# 10w_LED_driver_auto.net
KiCad netlist of a schematic drawn in EAGLE
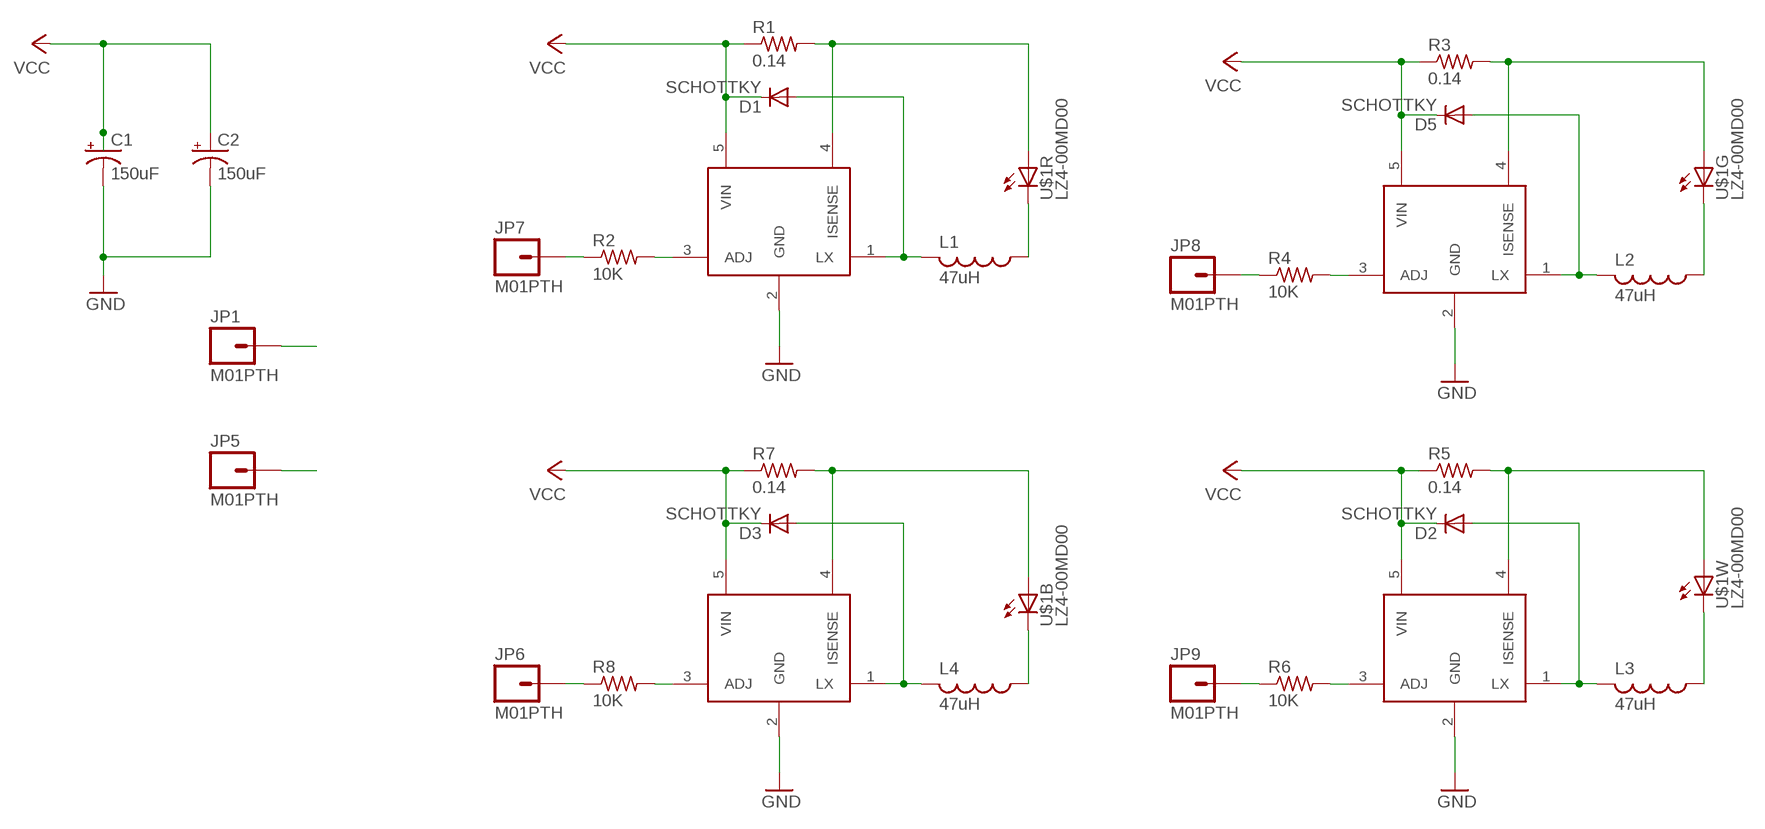
[diagram p0: schematic, sheet 1]

(export (version "E")
  (design (tool "Eeschema 10.0.6"))
  (components
    (comp (ref "C1")
      (value "150uF")
      (footprint "eagle-import:175TMP-0810")
      (libsource (lib "eagle-import") (part "CPOL-US175TMP-0810"))
    )
    (comp (ref "C2")
      (value "150uF")
      (footprint "eagle-import:175TMP-0810")
      (libsource (lib "eagle-import") (part "CPOL-US175TMP-0810"))
    )
    (comp (ref "D1")
      (value "SCHOTTKY")
      (footprint "eagle-import:DO214AC")
      (libsource (lib "eagle-import") (part "DIODE-DO214AC"))
    )
    (comp (ref "D2")
      (value "SCHOTTKY")
      (footprint "eagle-import:DO214AC")
      (libsource (lib "eagle-import") (part "DIODE-DO214AC"))
    )
    (comp (ref "D3")
      (value "SCHOTTKY")
      (footprint "eagle-import:DO214AC")
      (libsource (lib "eagle-import") (part "DIODE-DO214AC"))
    )
    (comp (ref "D5")
      (value "SCHOTTKY")
      (footprint "eagle-import:DO214AC")
      (libsource (lib "eagle-import") (part "DIODE-DO214AC"))
    )
    (comp (ref "JP1")
      (value "M01PTH")
      (footprint "eagle-import:1X01")
      (libsource (lib "eagle-import") (part "M01PTH"))
    )
    (comp (ref "JP5")
      (value "M01PTH")
      (footprint "eagle-import:1X01")
      (libsource (lib "eagle-import") (part "M01PTH"))
    )
    (comp (ref "JP6")
      (value "M01PTH")
      (footprint "eagle-import:1X01")
      (libsource (lib "eagle-import") (part "M01PTH"))
    )
    (comp (ref "JP7")
      (value "M01PTH")
      (footprint "eagle-import:1X01")
      (libsource (lib "eagle-import") (part "M01PTH"))
    )
    (comp (ref "JP8")
      (value "M01PTH")
      (footprint "eagle-import:1X01")
      (libsource (lib "eagle-import") (part "M01PTH"))
    )
    (comp (ref "JP9")
      (value "M01PTH")
      (footprint "eagle-import:1X01")
      (libsource (lib "eagle-import") (part "M01PTH"))
    )
    (comp (ref "L1")
      (value "47uH")
      (footprint "eagle-import:TDK6045")
      (libsource (lib "eagle-import") (part "L-US"))
    )
    (comp (ref "L2")
      (value "47uH")
      (footprint "eagle-import:TDK6045")
      (libsource (lib "eagle-import") (part "L-US"))
    )
    (comp (ref "L3")
      (value "47uH")
      (footprint "eagle-import:TDK6045")
      (libsource (lib "eagle-import") (part "L-US"))
    )
    (comp (ref "L4")
      (value "47uH")
      (footprint "eagle-import:TDK6045")
      (libsource (lib "eagle-import") (part "L-US"))
    )
    (comp (ref "R1")
      (value "0.14")
      (footprint "eagle-import:R0805")
      (libsource (lib "eagle-import") (part "R-US_R0805"))
    )
    (comp (ref "R2")
      (value "10K")
      (footprint "eagle-import:R0603")
      (libsource (lib "eagle-import") (part "R-US_R0603"))
    )
    (comp (ref "R3")
      (value "0.14")
      (footprint "eagle-import:R0805")
      (libsource (lib "eagle-import") (part "R-US_R0805"))
    )
    (comp (ref "R4")
      (value "10K")
      (footprint "eagle-import:R0603")
      (libsource (lib "eagle-import") (part "R-US_R0603"))
    )
    (comp (ref "R5")
      (value "0.14")
      (footprint "eagle-import:R0805")
      (libsource (lib "eagle-import") (part "R-US_R0805"))
    )
    (comp (ref "R6")
      (value "10K")
      (footprint "eagle-import:R0603")
      (libsource (lib "eagle-import") (part "R-US_R0603"))
    )
    (comp (ref "R7")
      (value "0.14")
      (footprint "eagle-import:R0805")
      (libsource (lib "eagle-import") (part "R-US_R0805"))
    )
    (comp (ref "R8")
      (value "10K")
      (footprint "eagle-import:R0603")
      (libsource (lib "eagle-import") (part "R-US_R0603"))
    )
    (comp (ref "U$1")
      (value "LZ4-00MD00")
      (footprint "eagle-import:LZ4-00MD0")
      (libsource (lib "eagle-import") (part "LZ4-00MD00"))
    )
    (comp (ref "U$2")
      (value "ZLED7000-LEDDRIVER")
      (footprint "eagle-import:SOT89-5")
      (libsource (lib "eagle-import") (part "ZLED7000-LEDDRIVER"))
    )
    (comp (ref "U$3")
      (value "ZLED7000-LEDDRIVER")
      (footprint "eagle-import:SOT89-5")
      (libsource (lib "eagle-import") (part "ZLED7000-LEDDRIVER"))
    )
    (comp (ref "U$4")
      (value "ZLED7000-LEDDRIVER")
      (footprint "eagle-import:SOT89-5")
      (libsource (lib "eagle-import") (part "ZLED7000-LEDDRIVER"))
    )
    (comp (ref "U$6")
      (value "ZLED7000-LEDDRIVER")
      (footprint "eagle-import:SOT89-5")
      (libsource (lib "eagle-import") (part "ZLED7000-LEDDRIVER"))
    )
  )
  (nets
    (net (code "1") (name "GND") (class "Default")
      (node (ref "C1") (pin "-") (pinfunction "-_-") (pintype "passive"))
      (node (ref "C2") (pin "-") (pinfunction "-_-") (pintype "passive"))
      (node (ref "JP5") (pin "1") (pinfunction "1_1") (pintype "passive"))
      (node (ref "U$2") (pin "2") (pinfunction "GND_2") (pintype "bidirectional"))
      (node (ref "U$3") (pin "2") (pinfunction "GND_2") (pintype "bidirectional"))
      (node (ref "U$4") (pin "2") (pinfunction "GND_2") (pintype "bidirectional"))
      (node (ref "U$6") (pin "2") (pinfunction "GND_2") (pintype "bidirectional"))
    )
    (net (code "2") (name "Net-(JP6-Pad1)") (class "Default")
      (node (ref "JP6") (pin "1") (pinfunction "1_1") (pintype "passive"))
      (node (ref "R8") (pin "1") (pinfunction "1_1") (pintype "passive"))
    )
    (net (code "3") (name "Net-(JP7-Pad1)") (class "Default")
      (node (ref "JP7") (pin "1") (pinfunction "1_1") (pintype "passive"))
      (node (ref "R2") (pin "1") (pinfunction "1_1") (pintype "passive"))
    )
    (net (code "4") (name "Net-(JP8-Pad1)") (class "Default")
      (node (ref "JP8") (pin "1") (pinfunction "1_1") (pintype "passive"))
      (node (ref "R4") (pin "1") (pinfunction "1_1") (pintype "passive"))
    )
    (net (code "5") (name "Net-(JP9-Pad1)") (class "Default")
      (node (ref "JP9") (pin "1") (pinfunction "1_1") (pintype "passive"))
      (node (ref "R6") (pin "1") (pinfunction "1_1") (pintype "passive"))
    )
    (net (code "6") (name "Net-(U$1A-A)") (class "Default")
      (node (ref "R7") (pin "2") (pinfunction "2_2") (pintype "passive"))
      (node (ref "U$1") (pin "7") (pinfunction "A_7") (pintype "passive"))
      (node (ref "U$4") (pin "4") (pinfunction "ISENSE_4") (pintype "bidirectional"))
    )
    (net (code "7") (name "Net-(U$1A-C)") (class "Default")
      (node (ref "L4") (pin "1") (pinfunction "1_1") (pintype "passive"))
      (node (ref "U$1") (pin "8") (pinfunction "C_8") (pintype "passive"))
    )
    (net (code "8") (name "Net-(U$1B-A)") (class "Default")
      (node (ref "R3") (pin "2") (pinfunction "2_2") (pintype "passive"))
      (node (ref "U$1") (pin "5") (pinfunction "A_5") (pintype "passive"))
      (node (ref "U$6") (pin "4") (pinfunction "ISENSE_4") (pintype "bidirectional"))
    )
    (net (code "9") (name "Net-(U$1B-C)") (class "Default")
      (node (ref "L2") (pin "1") (pinfunction "1_1") (pintype "passive"))
      (node (ref "U$1") (pin "6") (pinfunction "C_6") (pintype "passive"))
    )
    (net (code "10") (name "Net-(U$1C-A)") (class "Default")
      (node (ref "R1") (pin "2") (pinfunction "2_2") (pintype "passive"))
      (node (ref "U$1") (pin "3") (pinfunction "A_3") (pintype "passive"))
      (node (ref "U$2") (pin "4") (pinfunction "ISENSE_4") (pintype "bidirectional"))
    )
    (net (code "11") (name "Net-(U$1C-C)") (class "Default")
      (node (ref "L1") (pin "1") (pinfunction "1_1") (pintype "passive"))
      (node (ref "U$1") (pin "4") (pinfunction "C_4") (pintype "passive"))
    )
    (net (code "12") (name "Net-(U$1D-A)") (class "Default")
      (node (ref "R5") (pin "2") (pinfunction "2_2") (pintype "passive"))
      (node (ref "U$1") (pin "1") (pinfunction "A_1") (pintype "passive"))
      (node (ref "U$3") (pin "4") (pinfunction "ISENSE_4") (pintype "bidirectional"))
    )
    (net (code "13") (name "Net-(U$1D-C)") (class "Default")
      (node (ref "L3") (pin "1") (pinfunction "1_1") (pintype "passive"))
      (node (ref "U$1") (pin "2") (pinfunction "C_2") (pintype "passive"))
    )
    (net (code "14") (name "Net-(U$2-ADJ)") (class "Default")
      (node (ref "R2") (pin "2") (pinfunction "2_2") (pintype "passive"))
      (node (ref "U$2") (pin "3") (pinfunction "ADJ_3") (pintype "bidirectional"))
    )
    (net (code "15") (name "Net-(U$2-LX)") (class "Default")
      (node (ref "D1") (pin "A") (pinfunction "A_A") (pintype "passive"))
      (node (ref "L1") (pin "2") (pinfunction "2_2") (pintype "passive"))
      (node (ref "U$2") (pin "1") (pinfunction "LX_1") (pintype "bidirectional"))
    )
    (net (code "16") (name "Net-(U$3-ADJ)") (class "Default")
      (node (ref "R6") (pin "2") (pinfunction "2_2") (pintype "passive"))
      (node (ref "U$3") (pin "3") (pinfunction "ADJ_3") (pintype "bidirectional"))
    )
    (net (code "17") (name "Net-(U$3-LX)") (class "Default")
      (node (ref "D2") (pin "A") (pinfunction "A_A") (pintype "passive"))
      (node (ref "L3") (pin "2") (pinfunction "2_2") (pintype "passive"))
      (node (ref "U$3") (pin "1") (pinfunction "LX_1") (pintype "bidirectional"))
    )
    (net (code "18") (name "Net-(U$4-ADJ)") (class "Default")
      (node (ref "R8") (pin "2") (pinfunction "2_2") (pintype "passive"))
      (node (ref "U$4") (pin "3") (pinfunction "ADJ_3") (pintype "bidirectional"))
    )
    (net (code "19") (name "Net-(U$4-LX)") (class "Default")
      (node (ref "D3") (pin "A") (pinfunction "A_A") (pintype "passive"))
      (node (ref "L4") (pin "2") (pinfunction "2_2") (pintype "passive"))
      (node (ref "U$4") (pin "1") (pinfunction "LX_1") (pintype "bidirectional"))
    )
    (net (code "20") (name "Net-(U$6-ADJ)") (class "Default")
      (node (ref "R4") (pin "2") (pinfunction "2_2") (pintype "passive"))
      (node (ref "U$6") (pin "3") (pinfunction "ADJ_3") (pintype "bidirectional"))
    )
    (net (code "21") (name "Net-(U$6-LX)") (class "Default")
      (node (ref "D5") (pin "A") (pinfunction "A_A") (pintype "passive"))
      (node (ref "L2") (pin "2") (pinfunction "2_2") (pintype "passive"))
      (node (ref "U$6") (pin "1") (pinfunction "LX_1") (pintype "bidirectional"))
    )
    (net (code "22") (name "VCC") (class "Default")
      (node (ref "C1") (pin "+") (pinfunction "+_+") (pintype "passive"))
      (node (ref "C2") (pin "+") (pinfunction "+_+") (pintype "passive"))
      (node (ref "D1") (pin "C") (pinfunction "C_C") (pintype "passive"))
      (node (ref "D2") (pin "C") (pinfunction "C_C") (pintype "passive"))
      (node (ref "D3") (pin "C") (pinfunction "C_C") (pintype "passive"))
      (node (ref "D5") (pin "C") (pinfunction "C_C") (pintype "passive"))
      (node (ref "JP1") (pin "1") (pinfunction "1_1") (pintype "passive"))
      (node (ref "R1") (pin "1") (pinfunction "1_1") (pintype "passive"))
      (node (ref "R3") (pin "1") (pinfunction "1_1") (pintype "passive"))
      (node (ref "R5") (pin "1") (pinfunction "1_1") (pintype "passive"))
      (node (ref "R7") (pin "1") (pinfunction "1_1") (pintype "passive"))
      (node (ref "U$2") (pin "5") (pinfunction "VIN_5") (pintype "bidirectional"))
      (node (ref "U$3") (pin "5") (pinfunction "VIN_5") (pintype "bidirectional"))
      (node (ref "U$4") (pin "5") (pinfunction "VIN_5") (pintype "bidirectional"))
      (node (ref "U$6") (pin "5") (pinfunction "VIN_5") (pintype "bidirectional"))
    )
  )
)
